# 2_Power.net
KiCad netlist of a schematic drawn in Altium Designer
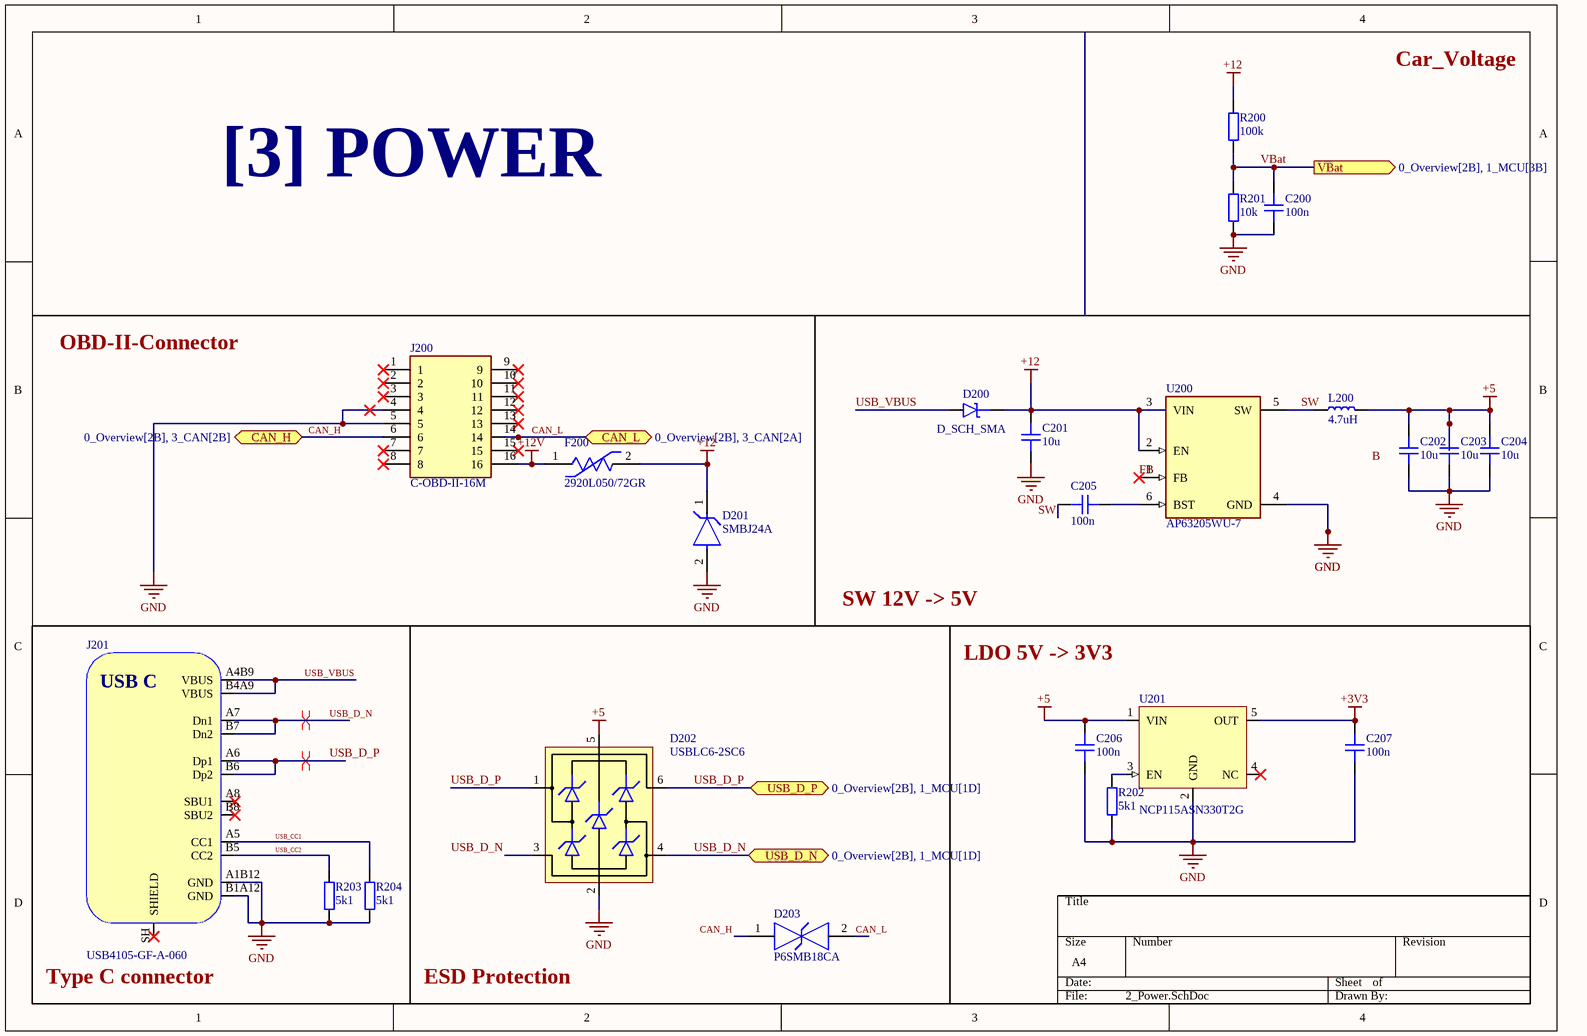
[diagram p0: 2_Power.SchDoc]

(export (version "E")
  (design (tool "Eeschema 10.0.6"))
  (components
    (comp (ref "C200")
      (value "100n")
      (footprint "CAP_0805")
      (description "Capacitor SMD 0805")
      (libsource (lib "Schematic-Lib-PhilsLab") (part "CAP_0805"))
    )
    (comp (ref "C201")
      (value "10u")
      (footprint "CAP_0805")
      (description "Capacitor SMD 0805")
      (libsource (lib "Schematic-Lib-PhilsLab") (part "CAP_0805"))
    )
    (comp (ref "C202")
      (value "10u")
      (footprint "CAP_0805")
      (description "Capacitor SMD 0805")
      (libsource (lib "Schematic-Lib-PhilsLab") (part "CAP_0805"))
    )
    (comp (ref "C203")
      (value "10u")
      (footprint "CAP_0805")
      (description "Capacitor SMD 0805")
      (libsource (lib "Schematic-Lib-PhilsLab") (part "CAP_0805"))
    )
    (comp (ref "C204")
      (value "10u")
      (footprint "CAP_0805")
      (description "Capacitor SMD 0805")
      (libsource (lib "Schematic-Lib-PhilsLab") (part "CAP_0805"))
    )
    (comp (ref "C205")
      (value "100n")
      (footprint "CAP_0603")
      (description "Capacitor SMD 0603")
      (libsource (lib "Schematic-Lib-PhilsLab") (part "CAP_0603"))
    )
    (comp (ref "C206")
      (value "100n")
      (footprint "CAP_0603")
      (description "Capacitor SMD 0603")
      (libsource (lib "Schematic-Lib-PhilsLab") (part "CAP_0603"))
    )
    (comp (ref "C207")
      (value "100n")
      (footprint "CAP_0603")
      (description "Capacitor SMD 0603")
      (libsource (lib "Schematic-Lib-PhilsLab") (part "CAP_0603"))
    )
    (comp (ref "D200")
      (value "D_SCH_SMA")
      (footprint "DO-214AC-2 (SMA)")
      (description "Diode Schottky SMD SMA (DO-214AA)")
      (libsource (lib "Schematic-Lib-PhilsLab") (part "D_SCHOTTKY_SMA"))
    )
    (comp (ref "D201")
      (value "SMBJ24A")
      (footprint "FP-SMBJ-MFG")
      (description "TVS DIODE 24V 38.9V SMB")
      (libsource (lib "Altium Content Vault") (part "f813f71cba58e380607f5dd3caf9714"))
    )
    (comp (ref "D202")
      (value "USBLC6-2SC6")
      (footprint "SOT-23-6")
      (description "Low-Capacitance ESD Protection USB")
      (fields (field (name "MANUFACTURER") "STMicroelectronics"))
      (libsource (lib "Schematic-Lib-PhilsLab") (part "USBLC6-2SC6"))
    )
    (comp (ref "D203")
      (value "P6SMB18CA")
      (footprint "FP-P6SMB-CA-MFG")
      (description "TVS DIODE 15.3V 25.5V DO214AA")
      (libsource (lib "Altium Content Vault") (part "876f4347bf90aa6f500f43e3cd03972"))
    )
    (comp (ref "F200")
      (value "2920L050/72GR")
      (footprint "FP-2920L-MFG")
      (description "PTC RESET FUSE 60V 1.1A 2920")
      (fields
        (field (name "MANUFACTURER PART NUMBER") "2920L110/60MR")
        (field (name "MANUFACTURER") "Littelfuse")
      )
      (libsource (lib "Altium Content Vault") (part "fc31388045fc42ab786d6d00b506e9f"))
    )
    (comp (ref "J200")
      (value "C-OBD-II-16M")
      (footprint "COMTECH_C-OBD-II-16M")
      (description "OBD II 16pin 90 Degree Angle Male Plug Connector")
      (fields (field (name "MF") "Comtech Electronic Co., LTD"))
      (libsource (lib "Ahmed ENP") (part "C-OBD-II-16M"))
    )
    (comp (ref "J201")
      (value "USB4105-GF-A-060")
      (footprint "USB4105-GF-A-060")
      (description "USB Connector Type C SMT 12 Pin")
      (fields (field (name "MANUFACTURER") "GCT"))
      (libsource (lib "Schematic-Lib-PhilsLab") (part "USB4105-GF-A-060"))
    )
    (comp (ref "L200")
      (value "4.7uH")
      (footprint "ASPI-4030S")
      (description "Power Inductor SMD ASPI-4030S Series")
      (fields (field (name "MANUFACTURER") "ABRACON") (field (name "MANUFACTURER PART NUMBER") "ASPI-4030S*"))
      (libsource (lib "Schematic-Lib-PhilsLab") (part "ASPI-4030S"))
    )
    (comp (ref "R200")
      (value "100k")
      (footprint "RES_0805")
      (description "Resistor SMD 0805")
      (libsource (lib "Schematic-Lib-PhilsLab") (part "RES_0805"))
    )
    (comp (ref "R201")
      (value "10k")
      (footprint "RES_0805")
      (description "Resistor SMD 0805")
      (libsource (lib "Schematic-Lib-PhilsLab") (part "RES_0805"))
    )
    (comp (ref "R202")
      (value "5k1")
      (footprint "RES_0603")
      (description "Resistor SMD 0603")
      (libsource (lib "Schematic-Lib-PhilsLab") (part "RES_0603"))
    )
    (comp (ref "R203")
      (value "5k1")
      (footprint "RES_0603")
      (description "Resistor SMD 0603")
      (libsource (lib "Schematic-Lib-PhilsLab") (part "RES_0603"))
    )
    (comp (ref "R204")
      (value "5k1")
      (footprint "RES_0603")
      (description "Resistor SMD 0603")
      (libsource (lib "Schematic-Lib-PhilsLab") (part "RES_0603"))
    )
    (comp (ref "U200")
      (value "AP63205WU-7")
      (footprint "FP-TSOT26-MFG")
      (description "IC REG BUCK 5V 2A TSOT26")
      (fields
        (field (name "MANUFACTURER") "Diodes Inc.")
        (field (name "OCTOPART") "https://octopart.com/ap63205wu-7-diodes+inc.-98099551")
      )
      (libsource (lib "Altium Content Vault") (part "029bc9fbfa4a99dbb8b3a24c2adb655"))
    )
    (comp (ref "U201")
      (value "NCP115ASN330T2G")
      (footprint "TSOT25")
      (description "LDO Regulator - High PSRR 300 mA 3.3V TSOP-5")
      (fields (field (name "MANUFACTURER") "ON Semiconductor"))
      (libsource (lib "Schematic-Lib-PhilsLab") (part "NCP115ASN330T2G"))
    )
  )
  (nets
    (net (code "1") (name "+3V3") (class "Default")
      (node (ref "C207") (pin "1") (pinfunction "1_1") (pintype "passive"))
      (node (ref "U201") (pin "5") (pinfunction "OUT_5") (pintype "power_in"))
    )
    (net (code "2") (name "+5") (class "Default")
      (node (ref "C202") (pin "2") (pinfunction "2_2") (pintype "passive"))
      (node (ref "C203") (pin "2") (pinfunction "2_2") (pintype "passive"))
      (node (ref "C204") (pin "2") (pinfunction "2_2") (pintype "passive"))
      (node (ref "C206") (pin "1") (pinfunction "1_1") (pintype "passive"))
      (node (ref "D202") (pin "5") (pinfunction "VBUS_5") (pintype "power_in"))
      (node (ref "L200") (pin "2") (pinfunction "2_2") (pintype "passive"))
      (node (ref "U201") (pin "1") (pinfunction "VIN_1") (pintype "power_in"))
    )
    (net (code "3") (name "+12") (class "Default")
      (node (ref "C201") (pin "2") (pinfunction "2_2") (pintype "passive"))
      (node (ref "D200") (pin "K") (pinfunction "K_K") (pintype "passive"))
      (node (ref "D201") (pin "1") (pinfunction "C_1") (pintype "passive"))
      (node (ref "F200") (pin "2") (pinfunction "2_2") (pintype "passive"))
      (node (ref "R200") (pin "2") (pinfunction "2_2") (pintype "passive"))
      (node (ref "U200") (pin "2") (pinfunction "EN_2") (pintype "input"))
      (node (ref "U200") (pin "3") (pinfunction "VIN_3") (pintype "power_in"))
    )
    (net (code "4") (name "+12V") (class "Default")
      (node (ref "F200") (pin "1") (pinfunction "1_1") (pintype "passive"))
      (node (ref "J200") (pin "16") (pinfunction "16_16") (pintype "passive"))
    )
    (net (code "6") (name "/CAN_H") (class "Default")
      (node (ref "D203") (pin "1") (pinfunction "1_1") (pintype "passive"))
      (node (ref "J200") (pin "6") (pinfunction "6_6") (pintype "passive"))
    )
    (net (code "7") (name "/CAN_L") (class "Default")
      (node (ref "D203") (pin "2") (pinfunction "2_2") (pintype "passive"))
      (node (ref "J200") (pin "14") (pinfunction "14_14") (pintype "passive"))
    )
    (net (code "8") (name "/FB") (class "Default")
      (node (ref "U200") (pin "1") (pinfunction "FB_1") (pintype "input+no_connect"))
    )
    (net (code "9") (name "/SW") (class "Default")
      (node (ref "C205") (pin "2") (pinfunction "2_2") (pintype "passive"))
      (node (ref "L200") (pin "1") (pinfunction "1_1") (pintype "passive"))
      (node (ref "U200") (pin "5") (pinfunction "SW_5") (pintype "power_in"))
    )
    (net (code "10") (name "/USB_CC1") (class "Default")
      (node (ref "J201") (pin "A5") (pinfunction "CC1_A5") (pintype "passive"))
      (node (ref "R204") (pin "2") (pinfunction "2_2") (pintype "passive"))
    )
    (net (code "11") (name "/USB_CC2") (class "Default")
      (node (ref "J201") (pin "B5") (pinfunction "CC2_B5") (pintype "passive"))
      (node (ref "R203") (pin "2") (pinfunction "2_2") (pintype "passive"))
    )
    (net (code "12") (name "/USB_D_N") (class "Default")
      (node (ref "D202") (pin "3") (pinfunction "IO2_3") (pintype "bidirectional"))
      (node (ref "D202") (pin "4") (pinfunction "IO2_4") (pintype "bidirectional"))
      (node (ref "J201") (pin "A7") (pinfunction "Dn1_A7") (pintype "passive"))
      (node (ref "J201") (pin "B7") (pinfunction "Dn2_B7") (pintype "passive"))
    )
    (net (code "13") (name "/USB_D_P") (class "Default")
      (node (ref "D202") (pin "1") (pinfunction "IO1_1") (pintype "bidirectional"))
      (node (ref "D202") (pin "6") (pinfunction "IO1_6") (pintype "bidirectional"))
      (node (ref "J201") (pin "A6") (pinfunction "Dp1_A6") (pintype "passive"))
      (node (ref "J201") (pin "B6") (pinfunction "Dp2_B6") (pintype "passive"))
    )
    (net (code "14") (name "/USB_VBUS") (class "Default")
      (node (ref "D200") (pin "A") (pinfunction "A_A") (pintype "passive"))
      (node (ref "J201") (pin "A4B9") (pinfunction "VBUS_A4B9") (pintype "passive"))
      (node (ref "J201") (pin "B4A9") (pinfunction "VBUS_B4A9") (pintype "passive"))
    )
    (net (code "15") (name "/VBat") (class "Default")
      (node (ref "C200") (pin "2") (pinfunction "2_2") (pintype "passive"))
      (node (ref "R200") (pin "1") (pinfunction "1_1") (pintype "passive"))
      (node (ref "R201") (pin "2") (pinfunction "2_2") (pintype "passive"))
    )
    (net (code "16") (name "GND") (class "Default")
      (node (ref "C200") (pin "1") (pinfunction "1_1") (pintype "passive"))
      (node (ref "C201") (pin "1") (pinfunction "1_1") (pintype "passive"))
      (node (ref "C202") (pin "1") (pinfunction "1_1") (pintype "passive"))
      (node (ref "C203") (pin "1") (pinfunction "1_1") (pintype "passive"))
      (node (ref "C204") (pin "1") (pinfunction "1_1") (pintype "passive"))
      (node (ref "C206") (pin "2") (pinfunction "2_2") (pintype "passive"))
      (node (ref "C207") (pin "2") (pinfunction "2_2") (pintype "passive"))
      (node (ref "D201") (pin "2") (pinfunction "A_2") (pintype "passive"))
      (node (ref "D202") (pin "2") (pinfunction "GND_2") (pintype "power_in"))
      (node (ref "J200") (pin "4") (pinfunction "4_4") (pintype "passive"))
      (node (ref "J200") (pin "5") (pinfunction "5_5") (pintype "passive"))
      (node (ref "J201") (pin "A1B12") (pinfunction "GND_A1B12") (pintype "passive"))
      (node (ref "J201") (pin "B1A12") (pinfunction "GND_B1A12") (pintype "passive"))
      (node (ref "R201") (pin "1") (pinfunction "1_1") (pintype "passive"))
      (node (ref "R202") (pin "1") (pinfunction "1_1") (pintype "passive"))
      (node (ref "R203") (pin "1") (pinfunction "1_1") (pintype "passive"))
      (node (ref "R204") (pin "1") (pinfunction "1_1") (pintype "passive"))
      (node (ref "U200") (pin "4") (pinfunction "GND_4") (pintype "power_in"))
      (node (ref "U201") (pin "2") (pinfunction "GND_2") (pintype "power_in"))
    )
    (net (code "17") (name "Net-(U200-BST)") (class "Default")
      (node (ref "C205") (pin "1") (pinfunction "1_1") (pintype "passive"))
      (node (ref "U200") (pin "6") (pinfunction "BST_6") (pintype "input"))
    )
    (net (code "18") (name "Net-(U201-EN)") (class "Default")
      (node (ref "R202") (pin "2") (pinfunction "2_2") (pintype "passive"))
      (node (ref "U201") (pin "3") (pinfunction "EN_3") (pintype "input"))
    )
    (net (code "19") (name "unconnected-(J200-Pad1)") (class "Default")
      (node (ref "J200") (pin "1") (pinfunction "1_1") (pintype "passive+no_connect"))
    )
    (net (code "20") (name "unconnected-(J200-Pad2)") (class "Default")
      (node (ref "J200") (pin "2") (pinfunction "2_2") (pintype "passive+no_connect"))
    )
    (net (code "21") (name "unconnected-(J200-Pad3)") (class "Default")
      (node (ref "J200") (pin "3") (pinfunction "3_3") (pintype "passive+no_connect"))
    )
    (net (code "22") (name "unconnected-(J200-Pad7)") (class "Default")
      (node (ref "J200") (pin "7") (pinfunction "7_7") (pintype "passive+no_connect"))
    )
    (net (code "23") (name "unconnected-(J200-Pad8)") (class "Default")
      (node (ref "J200") (pin "8") (pinfunction "8_8") (pintype "passive+no_connect"))
    )
    (net (code "24") (name "unconnected-(J200-Pad9)") (class "Default")
      (node (ref "J200") (pin "9") (pinfunction "9_9") (pintype "passive+no_connect"))
    )
    (net (code "25") (name "unconnected-(J200-Pad10)") (class "Default")
      (node (ref "J200") (pin "10") (pinfunction "10_10") (pintype "passive+no_connect"))
    )
    (net (code "26") (name "unconnected-(J200-Pad11)") (class "Default")
      (node (ref "J200") (pin "11") (pinfunction "11_11") (pintype "passive+no_connect"))
    )
    (net (code "27") (name "unconnected-(J200-Pad12)") (class "Default")
      (node (ref "J200") (pin "12") (pinfunction "12_12") (pintype "passive+no_connect"))
    )
    (net (code "28") (name "unconnected-(J200-Pad13)") (class "Default")
      (node (ref "J200") (pin "13") (pinfunction "13_13") (pintype "passive+no_connect"))
    )
    (net (code "29") (name "unconnected-(J200-Pad15)") (class "Default")
      (node (ref "J200") (pin "15") (pinfunction "15_15") (pintype "passive+no_connect"))
    )
    (net (code "30") (name "unconnected-(J201-SBU1-PadA8)") (class "Default")
      (node (ref "J201") (pin "A8") (pinfunction "SBU1_A8") (pintype "passive+no_connect"))
    )
    (net (code "31") (name "unconnected-(J201-SBU2-PadB8)") (class "Default")
      (node (ref "J201") (pin "B8") (pinfunction "SBU2_B8") (pintype "passive+no_connect"))
    )
    (net (code "32") (name "unconnected-(J201-SHIELD-PadSH)") (class "Default")
      (node (ref "J201") (pin "SH") (pinfunction "SHIELD_SH") (pintype "passive+no_connect"))
    )
    (net (code "33") (name "unconnected-(U201-NC-Pad4)") (class "Default")
      (node (ref "U201") (pin "4") (pinfunction "NC_4") (pintype "passive+no_connect"))
    )
  )
)
